# CAA-NMC-2.net
KiCad netlist of a schematic drawn in EAGLE
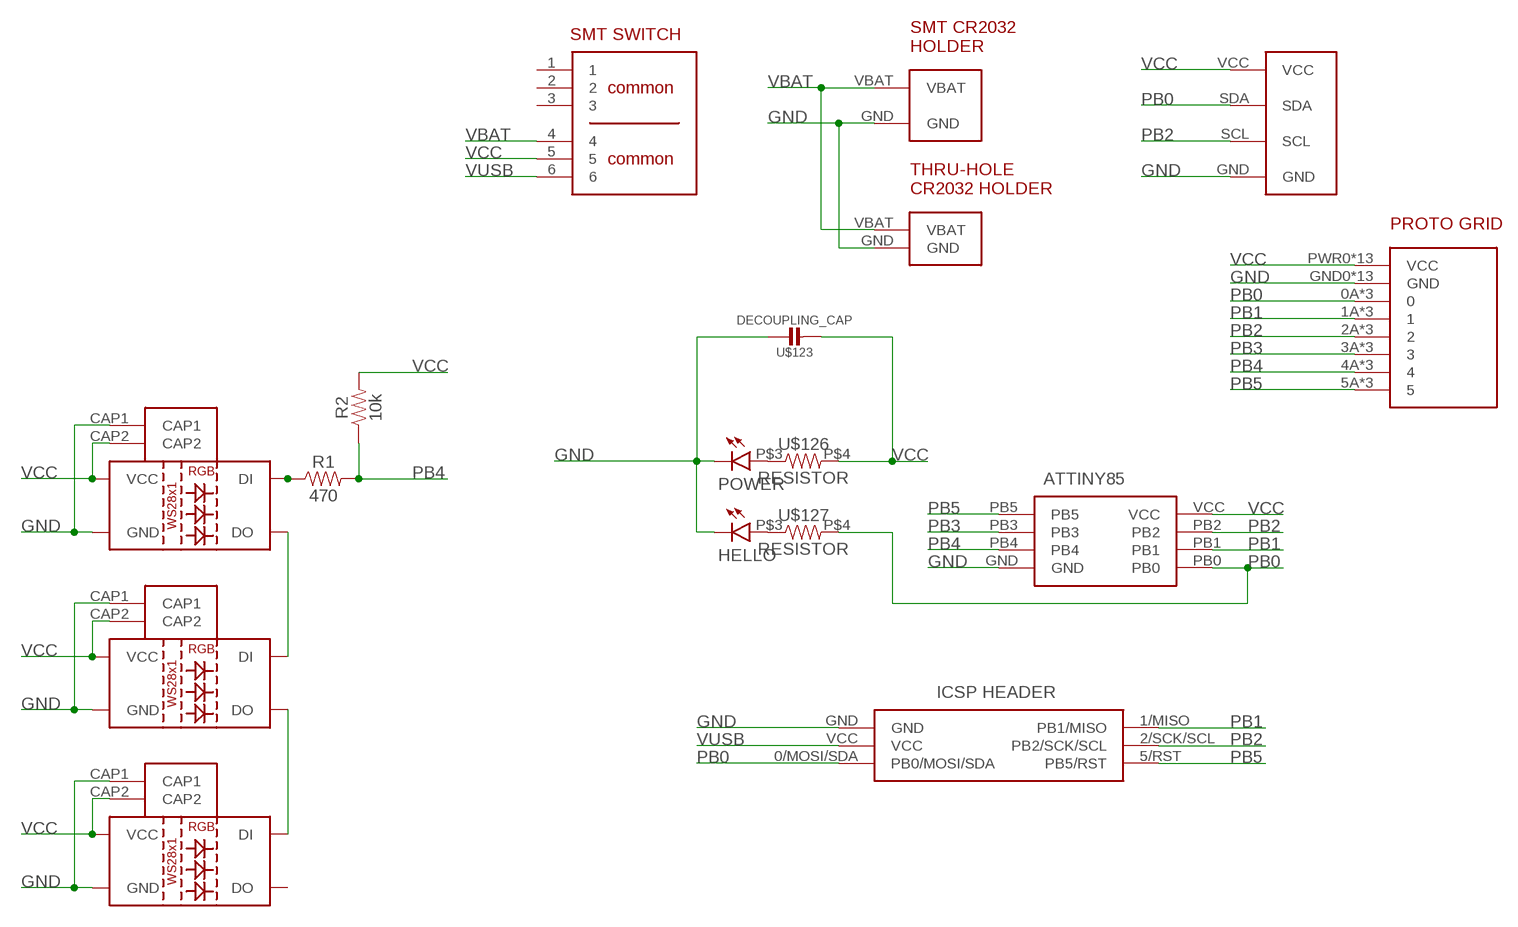
[diagram p0: schematic, sheet 1]

(export (version "E")
  (design (tool "Eeschema 10.0.6"))
  (components
    (comp (ref "D1")
      (value "WS2812B")
      (footprint "eagle-import:WS2812B")
      (libsource (lib "eagle-import") (part "WS2812B"))
    )
    (comp (ref "D2")
      (value "WS2812B")
      (footprint "eagle-import:WS2812B")
      (libsource (lib "eagle-import") (part "WS2812B"))
    )
    (comp (ref "D3")
      (value "WS2812B")
      (footprint "eagle-import:WS2812B")
      (libsource (lib "eagle-import") (part "WS2812B"))
    )
    (comp (ref "HELLO")
      (value "LED3MM")
      (footprint "eagle-import:LED3MM")
      (libsource (lib "eagle-import") (part "LED3MM"))
    )
    (comp (ref "IC1")
      (value "ATTINY85-20SU")
      (footprint "eagle-import:SOT127P798X216-8N")
      (fields (field (name "RS_PART_NUMBER") "1331674"))
      (libsource (lib "eagle-import") (part "ATTINY85-20SU"))
    )
    (comp (ref "J1")
      (value "M20-9980346")
      (footprint "eagle-import:HDRV6W64P254_2X3_762X508X868P")
      (fields (field (name "RS_PART_NUMBER") "7457046P"))
      (libsource (lib "eagle-import") (part "M20-9980346"))
    )
    (comp (ref "POWER")
      (value "LED3MM")
      (footprint "eagle-import:LED3MM")
      (libsource (lib "eagle-import") (part "LED3MM"))
    )
    (comp (ref "R1")
      (value "470")
      (footprint "eagle-import:0603")
      (libsource (lib "eagle-import") (part "470OHM-0603-1/10W-1%"))
    )
    (comp (ref "R2")
      (value "10k")
      (footprint "eagle-import:0603")
      (libsource (lib "eagle-import") (part "10KOHM-0603-1/10W-1%"))
    )
    (comp (ref "U$1")
      (value "PROTO")
      (footprint "eagle-import:PROTO")
      (libsource (lib "eagle-import") (part "PROTO"))
    )
    (comp (ref "U$2")
      (value "SMT-BATTERY-HOLDER")
      (footprint "eagle-import:SMT-CR-HOLDER")
      (libsource (lib "eagle-import") (part "SMT-BATTERY-HOLDER"))
    )
    (comp (ref "U$3")
      (value "THRU-CR-HOLDER")
      (footprint "eagle-import:THRU-CR-HOLDER")
      (libsource (lib "eagle-import") (part "THRU-CR-HOLDER"))
    )
    (comp (ref "U$4")
      (value "I2C-PADS")
      (footprint "eagle-import:I2C-PADS")
      (libsource (lib "eagle-import") (part "I2C-PADS"))
    )
    (comp (ref "U$123")
      (value "DECOUPLING_CAP")
      (footprint "eagle-import:DECOUPLING_CAP")
      (libsource (lib "eagle-import") (part "DECOUPLING_CAP"))
    )
    (comp (ref "U$126")
      (value "RESISTOR")
      (footprint "eagle-import:AXIAL-0.3")
      (libsource (lib "eagle-import") (part "RESISTOR"))
    )
    (comp (ref "U$127")
      (value "RESISTOR")
      (footprint "eagle-import:AXIAL-0.3")
      (libsource (lib "eagle-import") (part "RESISTOR"))
    )
    (comp (ref "U$145")
      (value "SMT-SWITCH")
      (footprint "eagle-import:SMT-SWITCH")
      (libsource (lib "eagle-import") (part "SMT-SWITCH"))
    )
  )
  (nets
    (net (code "1") (name "/GND") (class "Default")
      (node (ref "D1") (pin "CAP1") (pinfunction "CAP1_CAP1") (pintype "bidirectional"))
      (node (ref "D1") (pin "GND") (pinfunction "GND_GND") (pintype "bidirectional"))
      (node (ref "D2") (pin "CAP1") (pinfunction "CAP1_CAP1") (pintype "bidirectional"))
      (node (ref "D2") (pin "GND") (pinfunction "GND_GND") (pintype "bidirectional"))
      (node (ref "D3") (pin "CAP1") (pinfunction "CAP1_CAP1") (pintype "bidirectional"))
      (node (ref "D3") (pin "GND") (pinfunction "GND_GND") (pintype "bidirectional"))
      (node (ref "HELLO") (pin "NEG") (pinfunction "NEG_NEG") (pintype "passive"))
      (node (ref "IC1") (pin "GND") (pinfunction "GND_GND") (pintype "bidirectional"))
      (node (ref "J1") (pin "GND") (pinfunction "GND_GND") (pintype "bidirectional"))
      (node (ref "POWER") (pin "NEG") (pinfunction "NEG_NEG") (pintype "passive"))
      (node (ref "U$1") (pin "GND0") (pinfunction "GND_GND0") (pintype "bidirectional"))
      (node (ref "U$1") (pin "GND1") (pinfunction "GND_GND1") (pintype "bidirectional"))
      (node (ref "U$1") (pin "GND10") (pinfunction "GND_GND10") (pintype "bidirectional"))
      (node (ref "U$1") (pin "GND11") (pinfunction "GND_GND11") (pintype "bidirectional"))
      (node (ref "U$1") (pin "GND12") (pinfunction "GND_GND12") (pintype "bidirectional"))
      (node (ref "U$1") (pin "GND2") (pinfunction "GND_GND2") (pintype "bidirectional"))
      (node (ref "U$1") (pin "GND3") (pinfunction "GND_GND3") (pintype "bidirectional"))
      (node (ref "U$1") (pin "GND4") (pinfunction "GND_GND4") (pintype "bidirectional"))
      (node (ref "U$1") (pin "GND5") (pinfunction "GND_GND5") (pintype "bidirectional"))
      (node (ref "U$1") (pin "GND6") (pinfunction "GND_GND6") (pintype "bidirectional"))
      (node (ref "U$1") (pin "GND7") (pinfunction "GND_GND7") (pintype "bidirectional"))
      (node (ref "U$1") (pin "GND8") (pinfunction "GND_GND8") (pintype "bidirectional"))
      (node (ref "U$1") (pin "GND9") (pinfunction "GND_GND9") (pintype "bidirectional"))
      (node (ref "U$123") (pin "P$1") (pinfunction "1_P$1") (pintype "passive"))
      (node (ref "U$2") (pin "GND") (pinfunction "GND_GND") (pintype "bidirectional"))
      (node (ref "U$3") (pin "GND") (pinfunction "GND_GND") (pintype "bidirectional"))
      (node (ref "U$4") (pin "GND") (pinfunction "GND_GND") (pintype "bidirectional"))
    )
    (net (code "2") (name "/PB0") (class "Default")
      (node (ref "IC1") (pin "PB0") (pinfunction "PB0_PB0") (pintype "bidirectional"))
      (node (ref "J1") (pin "0/MOSI/SDA") (pinfunction "PB0/MOSI/SDA_0/MOSI/SDA") (pintype "bidirectional"))
      (node (ref "U$1") (pin "0A") (pinfunction "0_0A") (pintype "bidirectional"))
      (node (ref "U$1") (pin "0B") (pinfunction "0_0B") (pintype "bidirectional"))
      (node (ref "U$1") (pin "0C") (pinfunction "0_0C") (pintype "bidirectional"))
      (node (ref "U$127") (pin "P$4") (pinfunction "2_P$4") (pintype "passive"))
      (node (ref "U$4") (pin "SDA") (pinfunction "SDA_SDA") (pintype "bidirectional"))
    )
    (net (code "3") (name "/PB1") (class "Default")
      (node (ref "IC1") (pin "PB1") (pinfunction "PB1_PB1") (pintype "bidirectional"))
      (node (ref "J1") (pin "1/MISO") (pinfunction "PB1/MISO_1/MISO") (pintype "bidirectional"))
      (node (ref "U$1") (pin "1A") (pinfunction "1_1A") (pintype "bidirectional"))
      (node (ref "U$1") (pin "1B") (pinfunction "1_1B") (pintype "bidirectional"))
      (node (ref "U$1") (pin "1C") (pinfunction "1_1C") (pintype "bidirectional"))
    )
    (net (code "4") (name "/PB2") (class "Default")
      (node (ref "IC1") (pin "PB2") (pinfunction "PB2_PB2") (pintype "bidirectional"))
      (node (ref "J1") (pin "2/SCK/SCL") (pinfunction "PB2/SCK/SCL_2/SCK/SCL") (pintype "bidirectional"))
      (node (ref "U$1") (pin "2A") (pinfunction "2_2A") (pintype "bidirectional"))
      (node (ref "U$1") (pin "2B") (pinfunction "2_2B") (pintype "bidirectional"))
      (node (ref "U$1") (pin "2C") (pinfunction "2_2C") (pintype "bidirectional"))
      (node (ref "U$4") (pin "SCL") (pinfunction "SCL_SCL") (pintype "bidirectional"))
    )
    (net (code "5") (name "/PB3") (class "Default")
      (node (ref "IC1") (pin "PB3") (pinfunction "PB3_PB3") (pintype "bidirectional"))
      (node (ref "U$1") (pin "3A") (pinfunction "3_3A") (pintype "bidirectional"))
      (node (ref "U$1") (pin "3B") (pinfunction "3_3B") (pintype "bidirectional"))
      (node (ref "U$1") (pin "3C") (pinfunction "3_3C") (pintype "bidirectional"))
    )
    (net (code "6") (name "/PB4") (class "Default")
      (node (ref "IC1") (pin "PB4") (pinfunction "PB4_PB4") (pintype "bidirectional"))
      (node (ref "R1") (pin "2") (pinfunction "2_2") (pintype "passive"))
      (node (ref "R2") (pin "1") (pinfunction "1_1") (pintype "passive"))
      (node (ref "U$1") (pin "4A") (pinfunction "4_4A") (pintype "bidirectional"))
      (node (ref "U$1") (pin "4B") (pinfunction "4_4B") (pintype "bidirectional"))
      (node (ref "U$1") (pin "4C") (pinfunction "4_4C") (pintype "bidirectional"))
    )
    (net (code "7") (name "/PB5") (class "Default")
      (node (ref "IC1") (pin "PB5") (pinfunction "PB5_PB5") (pintype "bidirectional"))
      (node (ref "J1") (pin "5/RST") (pinfunction "PB5/RST_5/RST") (pintype "bidirectional"))
      (node (ref "U$1") (pin "5A") (pinfunction "5_5A") (pintype "bidirectional"))
      (node (ref "U$1") (pin "5B") (pinfunction "5_5B") (pintype "bidirectional"))
      (node (ref "U$1") (pin "5C") (pinfunction "5_5C") (pintype "bidirectional"))
    )
    (net (code "8") (name "/VBAT") (class "Default")
      (node (ref "U$145") (pin "4") (pinfunction "4_4") (pintype "bidirectional"))
      (node (ref "U$2") (pin "VBAT") (pinfunction "VBAT_VBAT") (pintype "bidirectional"))
      (node (ref "U$3") (pin "VBAT") (pinfunction "VBAT_VBAT") (pintype "bidirectional"))
    )
    (net (code "9") (name "/VCC") (class "Default")
      (node (ref "D1") (pin "CAP2") (pinfunction "CAP2_CAP2") (pintype "bidirectional"))
      (node (ref "D1") (pin "VCC") (pinfunction "VCC_VCC") (pintype "bidirectional"))
      (node (ref "D2") (pin "CAP2") (pinfunction "CAP2_CAP2") (pintype "bidirectional"))
      (node (ref "D2") (pin "VCC") (pinfunction "VCC_VCC") (pintype "bidirectional"))
      (node (ref "D3") (pin "CAP2") (pinfunction "CAP2_CAP2") (pintype "bidirectional"))
      (node (ref "D3") (pin "VCC") (pinfunction "VCC_VCC") (pintype "bidirectional"))
      (node (ref "IC1") (pin "VCC") (pinfunction "VCC_VCC") (pintype "bidirectional"))
      (node (ref "R2") (pin "2") (pinfunction "2_2") (pintype "passive"))
      (node (ref "U$1") (pin "PWR0") (pinfunction "VCC_PWR0") (pintype "bidirectional"))
      (node (ref "U$1") (pin "PWR1") (pinfunction "VCC_PWR1") (pintype "bidirectional"))
      (node (ref "U$1") (pin "PWR10") (pinfunction "VCC_PWR10") (pintype "bidirectional"))
      (node (ref "U$1") (pin "PWR11") (pinfunction "VCC_PWR11") (pintype "bidirectional"))
      (node (ref "U$1") (pin "PWR12") (pinfunction "VCC_PWR12") (pintype "bidirectional"))
      (node (ref "U$1") (pin "PWR2") (pinfunction "VCC_PWR2") (pintype "bidirectional"))
      (node (ref "U$1") (pin "PWR3") (pinfunction "VCC_PWR3") (pintype "bidirectional"))
      (node (ref "U$1") (pin "PWR4") (pinfunction "VCC_PWR4") (pintype "bidirectional"))
      (node (ref "U$1") (pin "PWR5") (pinfunction "VCC_PWR5") (pintype "bidirectional"))
      (node (ref "U$1") (pin "PWR6") (pinfunction "VCC_PWR6") (pintype "bidirectional"))
      (node (ref "U$1") (pin "PWR7") (pinfunction "VCC_PWR7") (pintype "bidirectional"))
      (node (ref "U$1") (pin "PWR8") (pinfunction "VCC_PWR8") (pintype "bidirectional"))
      (node (ref "U$1") (pin "PWR9") (pinfunction "VCC_PWR9") (pintype "bidirectional"))
      (node (ref "U$123") (pin "P$2") (pinfunction "2_P$2") (pintype "passive"))
      (node (ref "U$126") (pin "P$4") (pinfunction "2_P$4") (pintype "passive"))
      (node (ref "U$145") (pin "5") (pinfunction "5_5") (pintype "bidirectional"))
      (node (ref "U$4") (pin "VCC") (pinfunction "VCC_VCC") (pintype "bidirectional"))
    )
    (net (code "10") (name "/VUSB") (class "Default")
      (node (ref "J1") (pin "VCC") (pinfunction "VCC_VCC") (pintype "bidirectional"))
      (node (ref "U$145") (pin "6") (pinfunction "6_6") (pintype "bidirectional"))
    )
    (net (code "11") (name "Net-(D1-PadDI)") (class "Default")
      (node (ref "D1") (pin "DI") (pinfunction "DI_DI") (pintype "bidirectional"))
      (node (ref "R1") (pin "1") (pinfunction "1_1") (pintype "passive"))
    )
    (net (code "12") (name "Net-(D1-PadDO)") (class "Default")
      (node (ref "D1") (pin "DO") (pinfunction "DO_DO") (pintype "bidirectional"))
      (node (ref "D2") (pin "DI") (pinfunction "DI_DI") (pintype "bidirectional"))
    )
    (net (code "13") (name "Net-(D2-PadDO)") (class "Default")
      (node (ref "D2") (pin "DO") (pinfunction "DO_DO") (pintype "bidirectional"))
      (node (ref "D3") (pin "DI") (pinfunction "DI_DI") (pintype "bidirectional"))
    )
    (net (code "14") (name "Net-(U$126-1)") (class "Default")
      (node (ref "POWER") (pin "POS") (pinfunction "POS_POS") (pintype "passive"))
      (node (ref "U$126") (pin "P$3") (pinfunction "1_P$3") (pintype "passive"))
    )
    (net (code "15") (name "Net-(U$127-1)") (class "Default")
      (node (ref "HELLO") (pin "POS") (pinfunction "POS_POS") (pintype "passive"))
      (node (ref "U$127") (pin "P$3") (pinfunction "1_P$3") (pintype "passive"))
    )
    (net (code "16") (name "unconnected-(D3-PadDO)") (class "Default")
      (node (ref "D3") (pin "DO") (pinfunction "DO_DO") (pintype "bidirectional"))
    )
    (net (code "17") (name "unconnected-(U$145-Pad1)") (class "Default")
      (node (ref "U$145") (pin "1") (pinfunction "1_1") (pintype "bidirectional"))
    )
    (net (code "18") (name "unconnected-(U$145-Pad2)") (class "Default")
      (node (ref "U$145") (pin "2") (pinfunction "2_2") (pintype "bidirectional"))
    )
    (net (code "19") (name "unconnected-(U$145-Pad3)") (class "Default")
      (node (ref "U$145") (pin "3") (pinfunction "3_3") (pintype "bidirectional"))
    )
  )
)
